# AST-WiFi-Shield.net
KiCad netlist of a schematic drawn in EAGLE
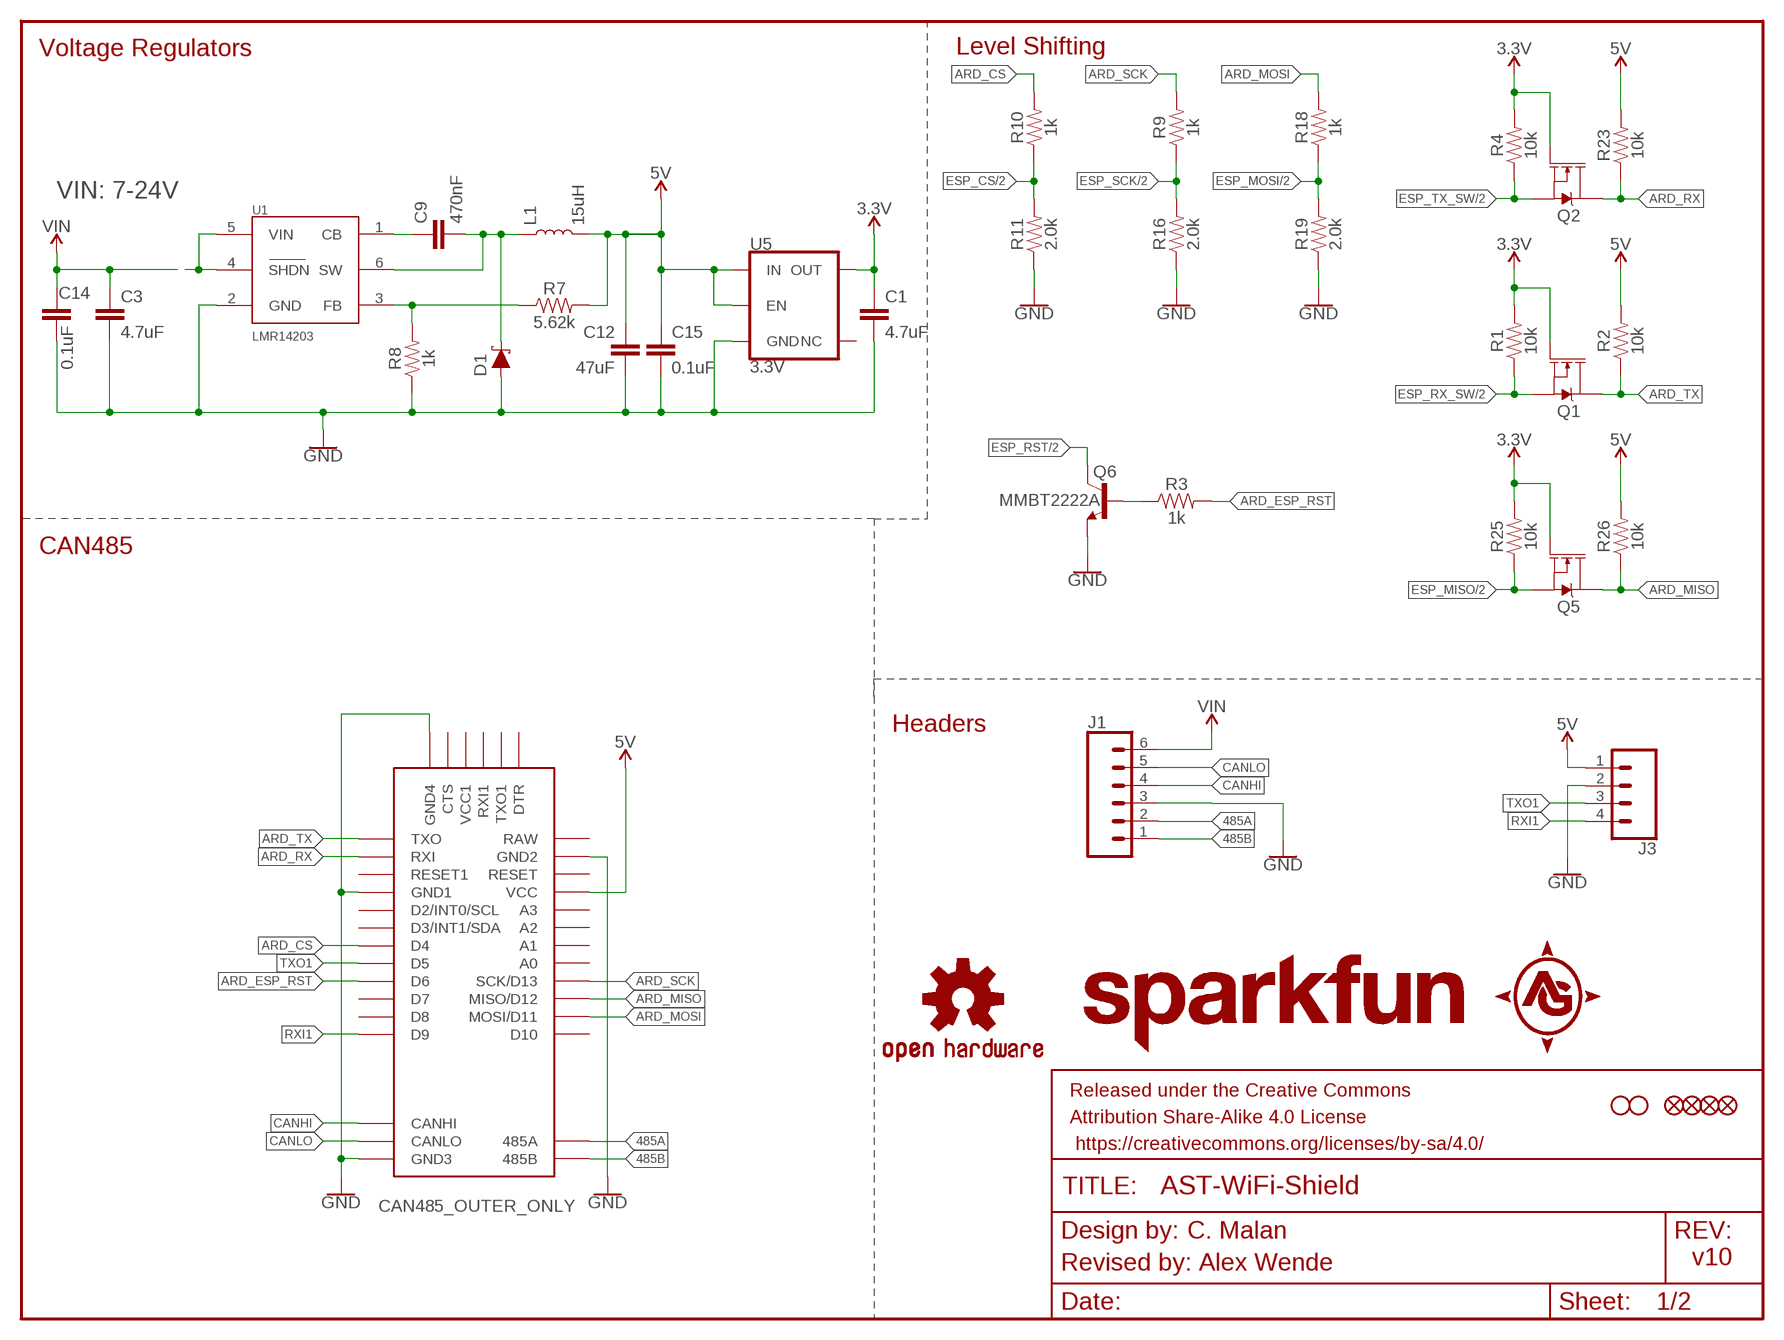
[diagram p0: schematic, sheet 1]
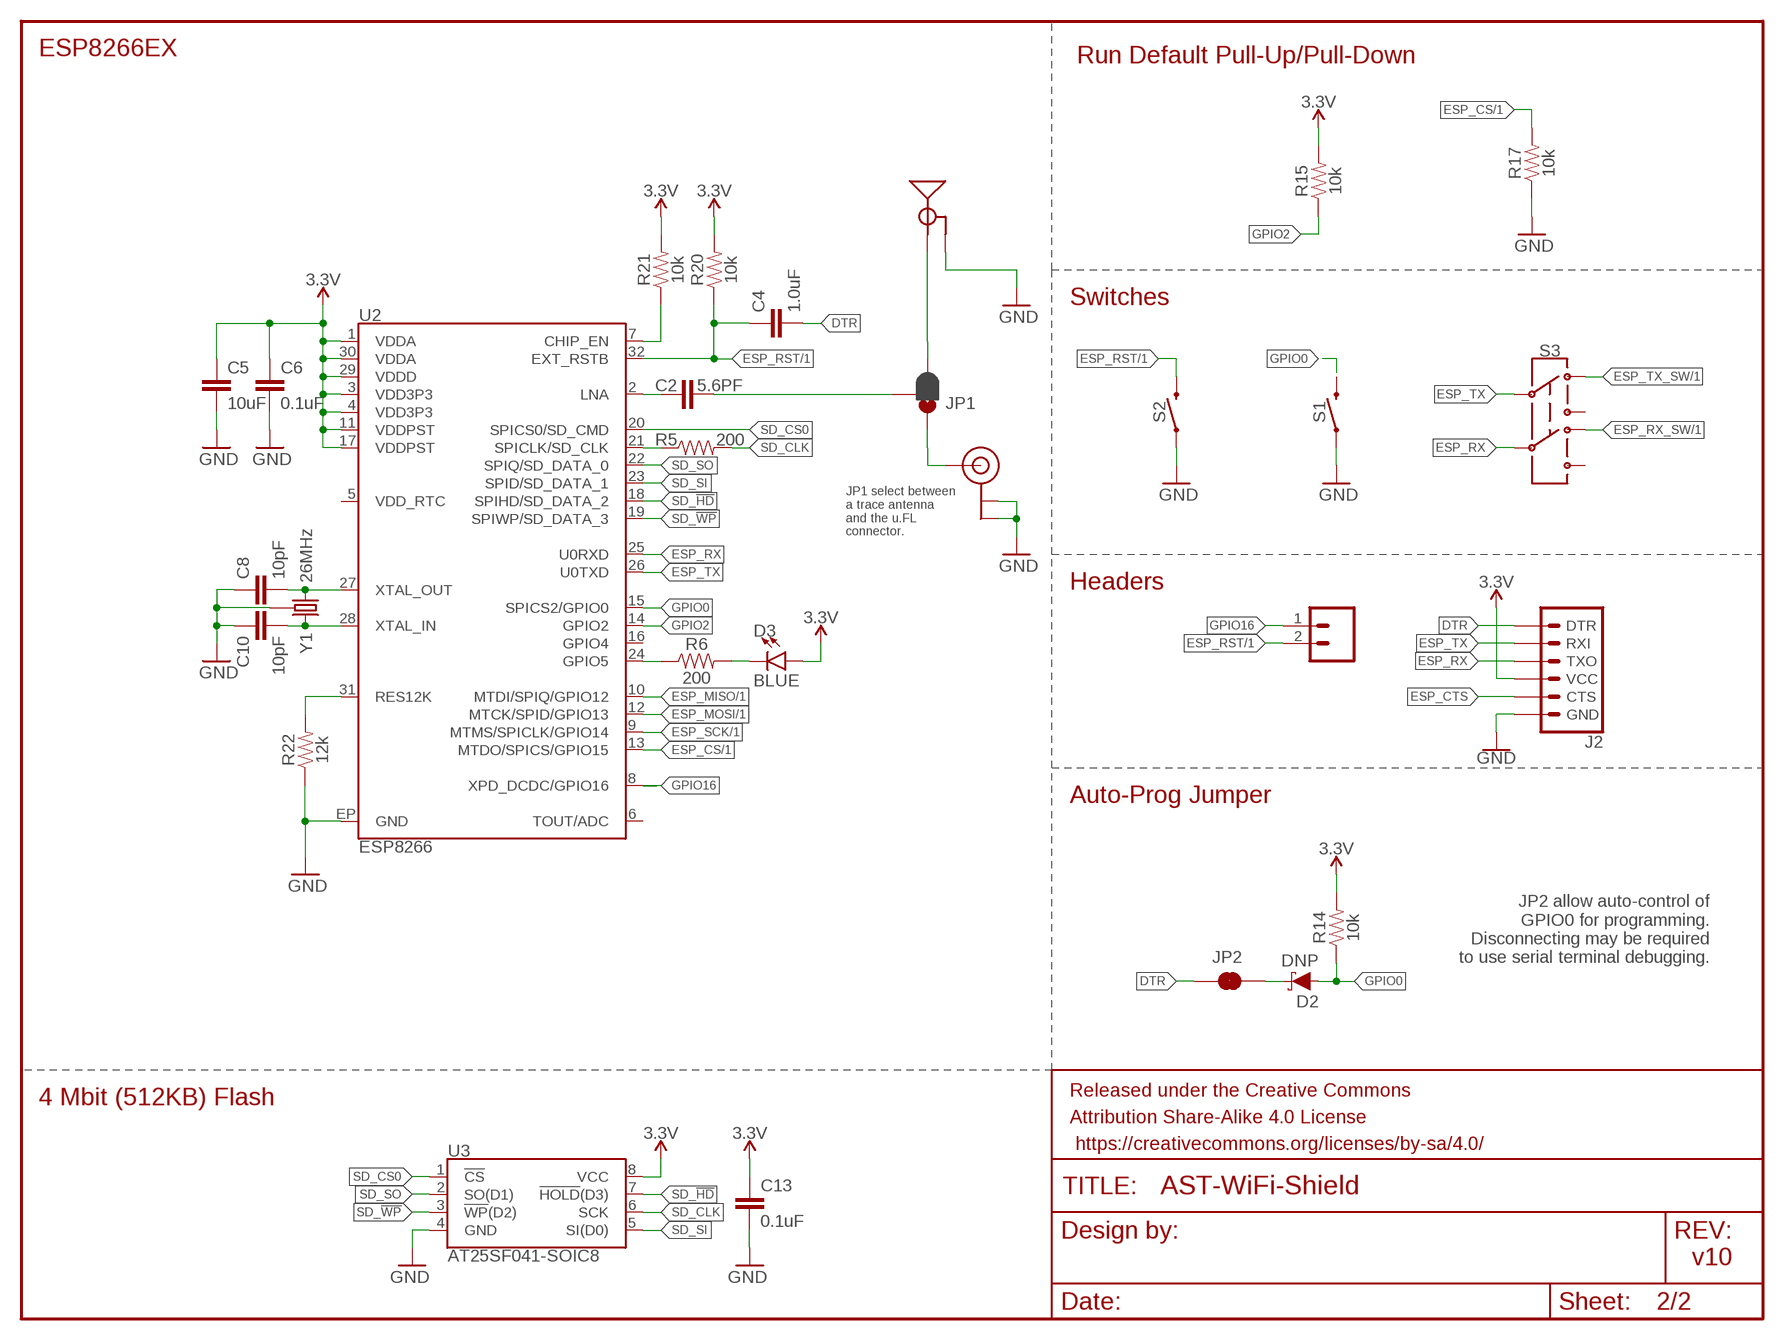
[diagram p1: schematic, sheet 2]

(export (version "E")
  (design (tool "Eeschema 10.0.6"))
  (components
    (comp (ref "C1")
      (value "4.7uF")
      (footprint "eagle-import:0603")
      (libsource (lib "eagle-import") (part "4.7UF-0603-6.3V-(10%)"))
    )
    (comp (ref "C3")
      (value "4.7uF")
      (footprint "eagle-import:0603")
      (libsource (lib "eagle-import") (part "4.7UF-0603-35V-(20%)"))
    )
    (comp (ref "C9")
      (value "470nF")
      (footprint "eagle-import:0603")
      (libsource (lib "eagle-import") (part "470NF-0603-10V-10%-X5R"))
    )
    (comp (ref "C12")
      (value "47uF")
      (footprint "eagle-import:0805")
      (libsource (lib "eagle-import") (part "47UF"))
    )
    (comp (ref "C14")
      (value "0.1uF")
      (footprint "eagle-import:0603")
      (libsource (lib "eagle-import") (part "0.1UF-0603-100V-10%"))
    )
    (comp (ref "C15")
      (value "0.1uF")
      (footprint "eagle-import:0603")
      (libsource (lib "eagle-import") (part "0.1UF-0603-25V-(+80/-20%)"))
    )
    (comp (ref "D1")
      (value "DIODE-SCHOTTKY-MSS1P6-M3/89A")
      (footprint "eagle-import:DIODE-MICRO-SMP")
      (libsource (lib "eagle-import") (part "DIODE-SCHOTTKY-MSS1P6-M3/89A"))
    )
    (comp (ref "FD1")
      (value "FIDUCIALUFIDUCIAL")
      (footprint "eagle-import:FIDUCIAL-MICRO")
      (libsource (lib "eagle-import") (part "FIDUCIALUFIDUCIAL"))
    )
    (comp (ref "FD2")
      (value "FIDUCIALUFIDUCIAL")
      (footprint "eagle-import:FIDUCIAL-MICRO")
      (libsource (lib "eagle-import") (part "FIDUCIALUFIDUCIAL"))
    )
    (comp (ref "FD3")
      (value "FIDUCIALUFIDUCIAL")
      (footprint "eagle-import:FIDUCIAL-MICRO")
      (libsource (lib "eagle-import") (part "FIDUCIALUFIDUCIAL"))
    )
    (comp (ref "FD4")
      (value "FIDUCIALUFIDUCIAL")
      (footprint "eagle-import:FIDUCIAL-MICRO")
      (libsource (lib "eagle-import") (part "FIDUCIALUFIDUCIAL"))
    )
    (comp (ref "FRAME2")
      (value "FRAME-LETTER")
      (footprint "eagle-import:CREATIVE_COMMONS")
      (libsource (lib "eagle-import") (part "FRAME-LETTER"))
    )
    (comp (ref "H1")
      (value "STAND-OFF")
      (footprint "eagle-import:STAND-OFF")
      (libsource (lib "eagle-import") (part "STAND-OFF"))
    )
    (comp (ref "H2")
      (value "STAND-OFF")
      (footprint "eagle-import:STAND-OFF")
      (libsource (lib "eagle-import") (part "STAND-OFF"))
    )
    (comp (ref "J1")
      (value "CONN_063.5MM-6")
      (footprint "eagle-import:SCREWTERMINAL-3.5MM-6")
      (libsource (lib "eagle-import") (part "CONN_063.5MM-6"))
    )
    (comp (ref "J3")
      (value "CONN_04LOCK")
      (footprint "eagle-import:1X04_LOCK")
      (libsource (lib "eagle-import") (part "CONN_04LOCK"))
    )
    (comp (ref "L1")
      (value "15uH")
      (footprint "eagle-import:INDUCTOR_LQH32")
      (libsource (lib "eagle-import") (part "INDUCTOR-LHQ32-15UH"))
    )
    (comp (ref "LOGO1")
      (value "OSHW-LOGOS")
      (footprint "eagle-import:OSHW-LOGO-S")
      (libsource (lib "eagle-import") (part "OSHW-LOGOS"))
    )
    (comp (ref "LOGO2")
      (value "SFE_LOGO_NAME.2_INCH")
      (footprint "eagle-import:SFE_LOGO_NAME_.2")
      (libsource (lib "eagle-import") (part "SFE_LOGO_NAME.2_INCH"))
    )
    (comp (ref "Q1")
      (value "220mA/50V/3.5Ω")
      (footprint "eagle-import:SOT23-3")
      (libsource (lib "eagle-import") (part "MOSFET-NCH-BSS138"))
    )
    (comp (ref "Q2")
      (value "220mA/50V/3.5Ω")
      (footprint "eagle-import:SOT23-3")
      (libsource (lib "eagle-import") (part "MOSFET-NCH-BSS138"))
    )
    (comp (ref "Q5")
      (value "220mA/50V/3.5Ω")
      (footprint "eagle-import:SOT23-3")
      (libsource (lib "eagle-import") (part "MOSFET-NCH-BSS138"))
    )
    (comp (ref "Q6")
      (value "MMBT2222A")
      (footprint "eagle-import:SOT23-3@1")
      (libsource (lib "eagle-import") (part "TRANSISTOR_NPNMMBT2222A"))
    )
    (comp (ref "R1")
      (value "10k")
      (footprint "eagle-import:0603")
      (libsource (lib "eagle-import") (part "10KOHM-0603-1/10W-1%"))
    )
    (comp (ref "R2")
      (value "10k")
      (footprint "eagle-import:0603")
      (libsource (lib "eagle-import") (part "10KOHM-0603-1/10W-1%"))
    )
    (comp (ref "R3")
      (value "1k")
      (footprint "eagle-import:0603")
      (libsource (lib "eagle-import") (part "1KOHM-0603-1/10W-1%"))
    )
    (comp (ref "R4")
      (value "10k")
      (footprint "eagle-import:0603")
      (libsource (lib "eagle-import") (part "10KOHM-0603-1/10W-1%"))
    )
    (comp (ref "R7")
      (value "5.62k")
      (footprint "eagle-import:0603")
      (libsource (lib "eagle-import") (part "5.62KOHM-0603-1/10W-1%"))
    )
    (comp (ref "R8")
      (value "1k")
      (footprint "eagle-import:0603")
      (libsource (lib "eagle-import") (part "1KOHM-0603-1/10W-1%"))
    )
    (comp (ref "R9")
      (value "1k")
      (footprint "eagle-import:0603")
      (libsource (lib "eagle-import") (part "1KOHM-0603-1/10W-1%"))
    )
    (comp (ref "R10")
      (value "1k")
      (footprint "eagle-import:0603")
      (libsource (lib "eagle-import") (part "1KOHM-0603-1/10W-1%"))
    )
    (comp (ref "R11")
      (value "2.0k")
      (footprint "eagle-import:0603")
      (libsource (lib "eagle-import") (part "2.0KOHM-0603-1/10W-5%"))
    )
    (comp (ref "R16")
      (value "2.0k")
      (footprint "eagle-import:0603")
      (libsource (lib "eagle-import") (part "2.0KOHM-0603-1/10W-5%"))
    )
    (comp (ref "R18")
      (value "1k")
      (footprint "eagle-import:0603")
      (libsource (lib "eagle-import") (part "1KOHM-0603-1/10W-1%"))
    )
    (comp (ref "R19")
      (value "2.0k")
      (footprint "eagle-import:0603")
      (libsource (lib "eagle-import") (part "2.0KOHM-0603-1/10W-5%"))
    )
    (comp (ref "R23")
      (value "10k")
      (footprint "eagle-import:0603")
      (libsource (lib "eagle-import") (part "10KOHM-0603-1/10W-1%"))
    )
    (comp (ref "R25")
      (value "10k")
      (footprint "eagle-import:0603")
      (libsource (lib "eagle-import") (part "10KOHM-0603-1/10W-1%"))
    )
    (comp (ref "R26")
      (value "10k")
      (footprint "eagle-import:0603")
      (libsource (lib "eagle-import") (part "10KOHM-0603-1/10W-1%"))
    )
    (comp (ref "U$2")
      (value "CAN485_OUTER_ONLY")
      (footprint "eagle-import:CAN485_OUTER_ONLY")
      (libsource (lib "eagle-import") (part "CAN485_OUTER_ONLY"))
    )
    (comp (ref "U1")
      (value "LMR14203")
      (footprint "eagle-import:SOT23-6")
      (libsource (lib "eagle-import") (part "LMR14203"))
    )
    (comp (ref "U5")
      (value "3.3V")
      (footprint "eagle-import:SOT23-5")
      (libsource (lib "eagle-import") (part "V_REG_AP2112K-3.3V"))
    )
    (comp (ref "C2")
      (value "5.6PF")
      (footprint "eagle-import:0603")
      (libsource (lib "eagle-import") (part "5.6PF-0603-50V-5%"))
    )
    (comp (ref "C4")
      (value "1.0uF")
      (footprint "eagle-import:0603")
      (libsource (lib "eagle-import") (part "1.0UF-0603-16V-10%"))
    )
    (comp (ref "C5")
      (value "10uF")
      (footprint "eagle-import:0603")
      (libsource (lib "eagle-import") (part "10UF-0603-6.3V-20%"))
    )
    (comp (ref "C6")
      (value "0.1uF")
      (footprint "eagle-import:0603")
      (libsource (lib "eagle-import") (part "0.1UF-0603-25V-(+80/-20%)"))
    )
    (comp (ref "C8")
      (value "10pF")
      (footprint "eagle-import:0603")
      (libsource (lib "eagle-import") (part "10PF-0603-50V-5%"))
    )
    (comp (ref "C10")
      (value "10pF")
      (footprint "eagle-import:0603")
      (libsource (lib "eagle-import") (part "10PF-0603-50V-5%"))
    )
    (comp (ref "C13")
      (value "0.1uF")
      (footprint "eagle-import:0603")
      (libsource (lib "eagle-import") (part "0.1UF-0603-25V-(+80/-20%)"))
    )
    (comp (ref "D2")
      (value "DNP")
      (footprint "eagle-import:SOD-323")
      (libsource (lib "eagle-import") (part "DIODE-SCHOTTKY-BAT20J"))
    )
    (comp (ref "D3")
      (value "BLUE")
      (footprint "eagle-import:LED-0603")
      (libsource (lib "eagle-import") (part "LED-BLUE0603"))
    )
    (comp (ref "E1")
      (value "ANTENNATRACE")
      (footprint "eagle-import:TRACE_ANTENNA_2.4GHZ_25.7MM")
      (libsource (lib "eagle-import") (part "ANTENNATRACE"))
    )
    (comp (ref "E2")
      (value "U.FL")
      (footprint "eagle-import:U.FL")
      (libsource (lib "eagle-import") (part "U.FL"))
    )
    (comp (ref "FRAME3")
      (value "FRAME-LETTERNO_PACKAGE")
      (footprint "eagle-import:DUMMY")
      (fields (field (name "DESIGNER") "Nobody"))
      (libsource (lib "eagle-import") (part "FRAME-LETTERNO_PACKAGE"))
    )
    (comp (ref "J2")
      (value "6_PIN_SERIAL_TARGETLOCK")
      (footprint "eagle-import:1X06_LOCK")
      (libsource (lib "eagle-import") (part "6_PIN_SERIAL_TARGETLOCK"))
    )
    (comp (ref "JP1")
      (value "JUMPER-SMT_3_1-NC_PASTE_NO-SILK")
      (footprint "eagle-import:SMT-JUMPER_3_1-NC_PASTE_NO-SILK")
      (libsource (lib "eagle-import") (part "JUMPER-SMT_3_1-NC_PASTE_NO-SILK"))
    )
    (comp (ref "JP2")
      (value "JUMPER-SMT_2_NC_TRACE_NO-SILK")
      (footprint "eagle-import:SMT-JUMPER_2_NC_TRACE_NO-SILK")
      (libsource (lib "eagle-import") (part "JUMPER-SMT_2_NC_TRACE_NO-SILK"))
    )
    (comp (ref "R5")
      (value "200")
      (footprint "eagle-import:0603")
      (libsource (lib "eagle-import") (part "200OHM-0603-1/10W-1%"))
    )
    (comp (ref "R6")
      (value "200")
      (footprint "eagle-import:0603")
      (libsource (lib "eagle-import") (part "200OHM-0603-1/10W-1%"))
    )
    (comp (ref "R14")
      (value "10k")
      (footprint "eagle-import:0603")
      (libsource (lib "eagle-import") (part "10KOHM-0603-1/10W-1%"))
    )
    (comp (ref "R15")
      (value "10k")
      (footprint "eagle-import:0603")
      (libsource (lib "eagle-import") (part "10KOHM-0603-1/10W-1%"))
    )
    (comp (ref "R17")
      (value "10k")
      (footprint "eagle-import:0603")
      (libsource (lib "eagle-import") (part "10KOHM-0603-1/10W-1%"))
    )
    (comp (ref "R20")
      (value "10k")
      (footprint "eagle-import:0603")
      (libsource (lib "eagle-import") (part "10KOHM-0603-1/10W-1%"))
    )
    (comp (ref "R21")
      (value "10k")
      (footprint "eagle-import:0603")
      (libsource (lib "eagle-import") (part "10KOHM-0603-1/10W-1%"))
    )
    (comp (ref "R22")
      (value "12k")
      (footprint "eagle-import:0603")
      (libsource (lib "eagle-import") (part "12KOHM-0603-1/10W-1%"))
    )
    (comp (ref "S1")
      (value "MOMENTARY-SWITCH-SPST-SMD-4.6X2.8MM")
      (footprint "eagle-import:TACTILE_SWITCH_SMD_4.6X2.8MM")
      (libsource (lib "eagle-import") (part "MOMENTARY-SWITCH-SPST-SMD-4.6X2.8MM"))
    )
    (comp (ref "S2")
      (value "MOMENTARY-SWITCH-SPST-SMD-4.6X2.8MM")
      (footprint "eagle-import:TACTILE_SWITCH_SMD_4.6X2.8MM")
      (libsource (lib "eagle-import") (part "MOMENTARY-SWITCH-SPST-SMD-4.6X2.8MM"))
    )
    (comp (ref "S3")
      (value "SWITCH-DPDT-SMD-JS202011JCQN")
      (footprint "eagle-import:SWITCH_DPDT_SMD_JS202011JCQN")
      (libsource (lib "eagle-import") (part "SWITCH-DPDT-SMD-JS202011JCQN"))
    )
    (comp (ref "SJ2")
      (value "SLEEP-PTH")
      (footprint "eagle-import:1X02_NO_SILK")
      (libsource (lib "eagle-import") (part "CONN_021X02_NO_SILK"))
    )
    (comp (ref "U2")
      (value "ESP8266")
      (footprint "eagle-import:QFN32")
      (fields (field (name "PROD_ID") "IC-12452"))
      (libsource (lib "eagle-import") (part "ESP8266"))
    )
    (comp (ref "U3")
      (value "AT25SF041-SOIC8")
      (footprint "eagle-import:SO08")
      (fields (field (name "PROD_ID") "IC-12455"))
      (libsource (lib "eagle-import") (part "AT25SF041-SOIC8"))
    )
    (comp (ref "Y1")
      (value "26MHz")
      (footprint "eagle-import:CRYSTAL-SMD-3.2X2.5")
      (fields (field (name "PROD_ID") "XTAL-12454"))
      (libsource (lib "eagle-import") (part "CRYSTAL-GROUNDED3.2X2.5"))
    )
  )
  (nets
    (net (code "1") (name "3.3V") (class "Default")
      (node (ref "C1") (pin "1") (pinfunction "1_1") (pintype "passive"))
      (node (ref "C13") (pin "1") (pinfunction "1_1") (pintype "passive"))
      (node (ref "C5") (pin "1") (pinfunction "1_1") (pintype "passive"))
      (node (ref "C6") (pin "1") (pinfunction "1_1") (pintype "passive"))
      (node (ref "D3") (pin "A") (pinfunction "A_A") (pintype "passive"))
      (node (ref "J2") (pin "4") (pinfunction "VCC_4") (pintype "passive"))
      (node (ref "Q1") (pin "1") (pinfunction "G_1") (pintype "bidirectional"))
      (node (ref "Q2") (pin "1") (pinfunction "G_1") (pintype "bidirectional"))
      (node (ref "Q5") (pin "1") (pinfunction "G_1") (pintype "bidirectional"))
      (node (ref "R1") (pin "2") (pinfunction "2_2") (pintype "passive"))
      (node (ref "R14") (pin "2") (pinfunction "2_2") (pintype "passive"))
      (node (ref "R15") (pin "2") (pinfunction "2_2") (pintype "passive"))
      (node (ref "R20") (pin "2") (pinfunction "2_2") (pintype "passive"))
      (node (ref "R21") (pin "2") (pinfunction "2_2") (pintype "passive"))
      (node (ref "R25") (pin "2") (pinfunction "2_2") (pintype "passive"))
      (node (ref "R4") (pin "2") (pinfunction "2_2") (pintype "passive"))
      (node (ref "U2") (pin "1") (pinfunction "VDDA_1") (pintype "bidirectional"))
      (node (ref "U2") (pin "11") (pinfunction "VDDPST_11") (pintype "bidirectional"))
      (node (ref "U2") (pin "17") (pinfunction "VDDPST_17") (pintype "bidirectional"))
      (node (ref "U2") (pin "29") (pinfunction "VDDD_29") (pintype "bidirectional"))
      (node (ref "U2") (pin "3") (pinfunction "VDD3P3_3") (pintype "bidirectional"))
      (node (ref "U2") (pin "30") (pinfunction "VDDA_30") (pintype "bidirectional"))
      (node (ref "U2") (pin "4") (pinfunction "VDD3P3_4") (pintype "bidirectional"))
      (node (ref "U3") (pin "8") (pinfunction "VCC_8") (pintype "bidirectional"))
      (node (ref "U5") (pin "5") (pinfunction "OUT_5") (pintype "passive"))
    )
    (net (code "2") (name "5V") (class "Default")
      (node (ref "C12") (pin "1") (pinfunction "1_1") (pintype "passive"))
      (node (ref "C15") (pin "1") (pinfunction "1_1") (pintype "passive"))
      (node (ref "J3") (pin "1") (pinfunction "1_1") (pintype "passive"))
      (node (ref "L1") (pin "P$2") (pinfunction "2_P$2") (pintype "passive"))
      (node (ref "R2") (pin "2") (pinfunction "2_2") (pintype "passive"))
      (node (ref "R23") (pin "2") (pinfunction "2_2") (pintype "passive"))
      (node (ref "R26") (pin "2") (pinfunction "2_2") (pintype "passive"))
      (node (ref "R7") (pin "2") (pinfunction "2_2") (pintype "passive"))
      (node (ref "U$2") (pin "VCC") (pinfunction "VCC_VCC") (pintype "bidirectional"))
      (node (ref "U5") (pin "1") (pinfunction "IN_1") (pintype "input"))
      (node (ref "U5") (pin "3") (pinfunction "EN_3") (pintype "input"))
    )
    (net (code "3") (name "485A") (class "Default")
      (node (ref "J1") (pin "2") (pinfunction "2_2") (pintype "passive"))
      (node (ref "U$2") (pin "485A") (pinfunction "485A_485A") (pintype "bidirectional"))
    )
    (net (code "4") (name "485B") (class "Default")
      (node (ref "J1") (pin "1") (pinfunction "1_1") (pintype "passive"))
      (node (ref "U$2") (pin "485B") (pinfunction "485B_485B") (pintype "bidirectional"))
    )
    (net (code "5") (name "ARD_CS") (class "Default")
      (node (ref "R10") (pin "2") (pinfunction "2_2") (pintype "passive"))
      (node (ref "U$2") (pin "4") (pinfunction "D4_4") (pintype "bidirectional"))
    )
    (net (code "6") (name "ARD_ESP_RST") (class "Default")
      (node (ref "R3") (pin "2") (pinfunction "2_2") (pintype "passive"))
      (node (ref "U$2") (pin "6") (pinfunction "D6_6") (pintype "bidirectional"))
    )
    (net (code "7") (name "ARD_MISO") (class "Default")
      (node (ref "Q5") (pin "3") (pinfunction "D_3") (pintype "bidirectional"))
      (node (ref "R26") (pin "1") (pinfunction "1_1") (pintype "passive"))
      (node (ref "U$2") (pin "12") (pinfunction "MISO/D12_12") (pintype "bidirectional"))
    )
    (net (code "8") (name "ARD_MOSI") (class "Default")
      (node (ref "R18") (pin "2") (pinfunction "2_2") (pintype "passive"))
      (node (ref "U$2") (pin "11") (pinfunction "MOSI/D11_11") (pintype "bidirectional"))
    )
    (net (code "9") (name "ARD_RX") (class "Default")
      (node (ref "Q2") (pin "3") (pinfunction "D_3") (pintype "bidirectional"))
      (node (ref "R23") (pin "1") (pinfunction "1_1") (pintype "passive"))
      (node (ref "U$2") (pin "RXI") (pinfunction "RXI_RXI") (pintype "bidirectional"))
    )
    (net (code "10") (name "ARD_SCK") (class "Default")
      (node (ref "R9") (pin "2") (pinfunction "2_2") (pintype "passive"))
      (node (ref "U$2") (pin "13") (pinfunction "SCK/D13_13") (pintype "bidirectional"))
    )
    (net (code "11") (name "ARD_TX") (class "Default")
      (node (ref "Q1") (pin "3") (pinfunction "D_3") (pintype "bidirectional"))
      (node (ref "R2") (pin "1") (pinfunction "1_1") (pintype "passive"))
      (node (ref "U$2") (pin "TXO") (pinfunction "TXO_TXO") (pintype "bidirectional"))
    )
    (net (code "12") (name "CANHI") (class "Default")
      (node (ref "J1") (pin "4") (pinfunction "4_4") (pintype "passive"))
      (node (ref "U$2") (pin "CANHI") (pinfunction "CANHI_CANHI") (pintype "bidirectional"))
    )
    (net (code "13") (name "CANLO") (class "Default")
      (node (ref "J1") (pin "5") (pinfunction "5_5") (pintype "passive"))
      (node (ref "U$2") (pin "CANLO") (pinfunction "CANLO_CANLO") (pintype "bidirectional"))
    )
    (net (code "14") (name "DTR") (class "Default")
      (node (ref "C4") (pin "2") (pinfunction "2_2") (pintype "passive"))
      (node (ref "J2") (pin "1") (pinfunction "DTR_1") (pintype "passive"))
      (node (ref "JP2") (pin "1") (pinfunction "1_1") (pintype "passive"))
    )
    (net (code "15") (name "ESP_CS") (class "Default")
      (node (ref "R10") (pin "1") (pinfunction "1_1") (pintype "passive"))
      (node (ref "R11") (pin "2") (pinfunction "2_2") (pintype "passive"))
      (node (ref "R17") (pin "2") (pinfunction "2_2") (pintype "passive"))
      (node (ref "U2") (pin "13") (pinfunction "MTDO/SPICS/GPIO15_13") (pintype "bidirectional"))
    )
    (net (code "16") (name "ESP_CTS") (class "Default")
      (node (ref "J2") (pin "5") (pinfunction "CTS_5") (pintype "passive"))
    )
    (net (code "17") (name "ESP_MISO") (class "Default")
      (node (ref "Q5") (pin "2") (pinfunction "S_2") (pintype "bidirectional"))
      (node (ref "R25") (pin "1") (pinfunction "1_1") (pintype "passive"))
      (node (ref "U2") (pin "10") (pinfunction "MTDI/SPIQ/GPIO12_10") (pintype "bidirectional"))
    )
    (net (code "18") (name "ESP_MOSI") (class "Default")
      (node (ref "R18") (pin "1") (pinfunction "1_1") (pintype "passive"))
      (node (ref "R19") (pin "2") (pinfunction "2_2") (pintype "passive"))
      (node (ref "U2") (pin "12") (pinfunction "MTCK/SPID/GPIO13_12") (pintype "bidirectional"))
    )
    (net (code "19") (name "ESP_RST") (class "Default")
      (node (ref "C4") (pin "1") (pinfunction "1_1") (pintype "passive"))
      (node (ref "Q6") (pin "3") (pinfunction "C_3") (pintype "passive"))
      (node (ref "R20") (pin "1") (pinfunction "1_1") (pintype "passive"))
      (node (ref "S2") (pin "3") (pinfunction "2_3") (pintype "passive"))
      (node (ref "S2") (pin "4") (pinfunction "2_4") (pintype "passive"))
      (node (ref "SJ2") (pin "2") (pinfunction "2_2") (pintype "passive"))
      (node (ref "U2") (pin "32") (pinfunction "EXT_RSTB_32") (pintype "bidirectional"))
    )
    (net (code "20") (name "ESP_RX") (class "Default")
      (node (ref "J2") (pin "3") (pinfunction "TXO_3") (pintype "passive"))
      (node (ref "S3") (pin "5") (pinfunction "5_5") (pintype "bidirectional"))
      (node (ref "U2") (pin "25") (pinfunction "U0RXD_25") (pintype "bidirectional"))
    )
    (net (code "21") (name "ESP_RX_SW") (class "Default")
      (node (ref "Q1") (pin "2") (pinfunction "S_2") (pintype "bidirectional"))
      (node (ref "R1") (pin "1") (pinfunction "1_1") (pintype "passive"))
      (node (ref "S3") (pin "6") (pinfunction "4_6") (pintype "bidirectional"))
    )
    (net (code "22") (name "ESP_SCK") (class "Default")
      (node (ref "R16") (pin "2") (pinfunction "2_2") (pintype "passive"))
      (node (ref "R9") (pin "1") (pinfunction "1_1") (pintype "passive"))
      (node (ref "U2") (pin "9") (pinfunction "MTMS/SPICLK/GPIO14_9") (pintype "bidirectional"))
    )
    (net (code "23") (name "ESP_TX") (class "Default")
      (node (ref "J2") (pin "2") (pinfunction "RXI_2") (pintype "passive"))
      (node (ref "S3") (pin "2") (pinfunction "2_2") (pintype "bidirectional"))
      (node (ref "U2") (pin "26") (pinfunction "U0TXD_26") (pintype "bidirectional"))
    )
    (net (code "24") (name "ESP_TX_SW") (class "Default")
      (node (ref "Q2") (pin "2") (pinfunction "S_2") (pintype "bidirectional"))
      (node (ref "R4") (pin "1") (pinfunction "1_1") (pintype "passive"))
      (node (ref "S3") (pin "1") (pinfunction "1_1") (pintype "bidirectional"))
    )
    (net (code "25") (name "GND") (class "Default")
      (node (ref "C1") (pin "2") (pinfunction "2_2") (pintype "passive"))
      (node (ref "C10") (pin "1") (pinfunction "1_1") (pintype "passive"))
      (node (ref "C12") (pin "2") (pinfunction "2_2") (pintype "passive"))
      (node (ref "C13") (pin "2") (pinfunction "2_2") (pintype "passive"))
      (node (ref "C14") (pin "2") (pinfunction "2_2") (pintype "passive"))
      (node (ref "C15") (pin "2") (pinfunction "2_2") (pintype "passive"))
      (node (ref "C3") (pin "2") (pinfunction "2_2") (pintype "passive"))
      (node (ref "C5") (pin "2") (pinfunction "2_2") (pintype "passive"))
      (node (ref "C6") (pin "2") (pinfunction "2_2") (pintype "passive"))
      (node (ref "C8") (pin "1") (pinfunction "1_1") (pintype "passive"))
      (node (ref "D1") (pin "A") (pinfunction "A_A") (pintype "passive"))
      (node (ref "E1") (pin "GND") (pinfunction "GND_GND") (pintype "bidirectional"))
      (node (ref "E1") (pin "GND2") (pinfunction "GND_GND2") (pintype "bidirectional"))
      (node (ref "E2") (pin "1") (pinfunction "GND_1") (pintype "bidirectional"))
      (node (ref "E2") (pin "2") (pinfunction "GND_2") (pintype "bidirectional"))
      (node (ref "J1") (pin "3") (pinfunction "3_3") (pintype "passive"))
      (node (ref "J2") (pin "6") (pinfunction "GND_6") (pintype "passive"))
      (node (ref "J3") (pin "2") (pinfunction "2_2") (pintype "passive"))
      (node (ref "Q6") (pin "2") (pinfunction "E_2") (pintype "passive"))
      (node (ref "R11") (pin "1") (pinfunction "1_1") (pintype "passive"))
      (node (ref "R16") (pin "1") (pinfunction "1_1") (pintype "passive"))
      (node (ref "R17") (pin "1") (pinfunction "1_1") (pintype "passive"))
      (node (ref "R19") (pin "1") (pinfunction "1_1") (pintype "passive"))
      (node (ref "R22") (pin "1") (pinfunction "1_1") (pintype "passive"))
      (node (ref "R8") (pin "1") (pinfunction "1_1") (pintype "passive"))
      (node (ref "S1") (pin "1") (pinfunction "1_1") (pintype "passive"))
      (node (ref "S1") (pin "2") (pinfunction "1_2") (pintype "passive"))
      (node (ref "S2") (pin "1") (pinfunction "1_1") (pintype "passive"))
      (node (ref "S2") (pin "2") (pinfunction "1_2") (pintype "passive"))
      (node (ref "U$2") (pin "GND1") (pinfunction "GND1_GND1") (pintype "bidirectional"))
      (node (ref "U$2") (pin "GND2") (pinfunction "GND2_GND2") (pintype "bidirectional"))
      (node (ref "U$2") (pin "GND3") (pinfunction "GND3_GND3") (pintype "bidirectional"))
      (node (ref "U$2") (pin "GND4") (pinfunction "GND4_GND4") (pintype "bidirectional"))
      (node (ref "U1") (pin "2") (pinfunction "GND_2") (pintype "power_in"))
      (node (ref "U2") (pin "EP") (pinfunction "GND_EP") (pintype "bidirectional"))
      (node (ref "U3") (pin "4") (pinfunction "GND_4") (pintype "bidirectional"))
      (node (ref "U5") (pin "2") (pinfunction "GND_2") (pintype "input"))
      (node (ref "Y1") (pin "2") (pinfunction "GND_2") (pintype "passive"))
      (node (ref "Y1") (pin "4") (pinfunction "GND_4") (pintype "passive"))
    )
    (net (code "26") (name "GPIO0") (class "Default")
      (node (ref "D2") (pin "A") (pinfunction "A_A") (pintype "passive"))
      (node (ref "R14") (pin "1") (pinfunction "1_1") (pintype "passive"))
      (node (ref "S1") (pin "3") (pinfunction "2_3") (pintype "passive"))
      (node (ref "S1") (pin "4") (pinfunction "2_4") (pintype "passive"))
      (node (ref "U2") (pin "15") (pinfunction "SPICS2/GPIO0_15") (pintype "bidirectional"))
    )
    (net (code "27") (name "GPIO2") (class "Default")
      (node (ref "R15") (pin "1") (pinfunction "1_1") (pintype "passive"))
      (node (ref "U2") (pin "14") (pinfunction "GPIO2_14") (pintype "bidirectional"))
    )
    (net (code "28") (name "GPIO16") (class "Default")
      (node (ref "SJ2") (pin "1") (pinfunction "1_1") (pintype "passive"))
      (node (ref "U2") (pin "8") (pinfunction "XPD_DCDC/GPIO16_8") (pintype "bidirectional"))
    )
    (net (code "29") (name "Net-(C2-Pad2)") (class "Default")
      (node (ref "C2") (pin "2") (pinfunction "2_2") (pintype "passive"))
      (node (ref "JP1") (pin "2") (pinfunction "2_2") (pintype "passive"))
    )
    (net (code "30") (name "Net-(D2-PadC)") (class "Default")
      (node (ref "D2") (pin "C") (pinfunction "C_C") (pintype "passive"))
      (node (ref "JP2") (pin "2") (pinfunction "2_2") (pintype "passive"))
    )
    (net (code "31") (name "Net-(D3-PadC)") (class "Default")
      (node (ref "D3") (pin "C") (pinfunction "C_C") (pintype "passive"))
      (node (ref "R6") (pin "2") (pinfunction "2_2") (pintype "passive"))
    )
    (net (code "32") (name "Net-(E1-SIGNAL)") (class "Default")
      (node (ref "E1") (pin "ANT") (pinfunction "SIGNAL_ANT") (pintype "bidirectional"))
      (node (ref "JP1") (pin "3") (pinfunction "3_3") (pintype "passive"))
    )
    (net (code "33") (name "Net-(E2-SIGNAL)") (class "Default")
      (node (ref "E2") (pin "FEED") (pinfunction "SIGNAL_FEED") (pintype "bidirectional"))
      (node (ref "JP1") (pin "1") (pinfunction "1_1") (pintype "passive"))
    )
    (net (code "34") (name "Net-(L1-1)") (class "Default")
      (node (ref "C9") (pin "2") (pinfunction "2_2") (pintype "passive"))
      (node (ref "D1") (pin "C") (pinfunction "C_C") (pintype "passive"))
      (node (ref "L1") (pin "P$1") (pinfunction "1_P$1") (pintype "passive"))
      (node (ref "U1") (pin "6") (pinfunction "SW_6") (pintype "power_in"))
    )
    (net (code "35") (name "Net-(Q6-B)") (class "Default")
      (node (ref "Q6") (pin "1") (pinfunction "B_1") (pintype "passive"))
      (node (ref "R3") (pin "1") (pinfunction "1_1") (pintype "passive"))
    )
    (net (code "36") (name "Net-(U1-CB)") (class "Default")
      (node (ref "C9") (pin "1") (pinfunction "1_1") (pintype "passive"))
      (node (ref "U1") (pin "1") (pinfunction "CB_1") (pintype "input"))
    )
    (net (code "37") (name "Net-(U1-FB)") (class "Default")
      (node (ref "R7") (pin "1") (pinfunction "1_1") (pintype "passive"))
      (node (ref "R8") (pin "2") (pinfunction "2_2") (pintype "passive"))
      (node (ref "U1") (pin "3") (pinfunction "FB_3") (pintype "input"))
    )
    (net (code "38") (name "Net-(U2-CHIP_EN)") (class "Default")
      (node (ref "R21") (pin "1") (pinfunction "1_1") (pintype "passive"))
      (node (ref "U2") (pin "7") (pinfunction "CHIP_EN_7") (pintype "bidirectional"))
    )
    (net (code "39") (name "Net-(U2-GPIO5)") (class "Default")
      (node (ref "R6") (pin "1") (pinfunction "1_1") (pintype "passive"))
      (node (ref "U2") (pin "24") (pinfunction "GPIO5_24") (pintype "bidirectional"))
    )
    (net (code "40") (name "Net-(U2-LNA)") (class "Default")
      (node (ref "C2") (pin "1") (pinfunction "1_1") (pintype "passive"))
      (node (ref "U2") (pin "2") (pinfunction "LNA_2") (pintype "bidirectional"))
    )
    (net (code "41") (name "Net-(U2-RES12K)") (class "Default")
      (node (ref "R22") (pin "2") (pinfunction "2_2") (pintype "passive"))
      (node (ref "U2") (pin "31") (pinfunction "RES12K_31") (pintype "bidirectional"))
    )
    (net (code "42") (name "Net-(U2-SPICLK{slash}SD_CLK)") (class "Default")
      (node (ref "R5") (pin "1") (pinfunction "1_1") (pintype "passive"))
      (node (ref "U2") (pin "21") (pinfunction "SPICLK/SD_CLK_21") (pintype "bidirectional"))
    )
    (net (code "43") (name "Net-(U2-XTAL_IN)") (class "Default")
      (node (ref "C10") (pin "2") (pinfunction "2_2") (pintype "passive"))
      (node (ref "U2") (pin "28") (pinfunction "XTAL_IN_28") (pintype "bidirectional"))
      (node (ref "Y1") (pin "3") (pinfunction "2_3") (pintype "passive"))
    )
    (net (code "44") (name "Net-(U2-XTAL_OUT)") (class "Default")
      (node (ref "C8") (pin "2") (pinfunction "2_2") (pintype "passive"))
      (node (ref "U2") (pin "27") (pinfunction "XTAL_OUT_27") (pintype "bidirectional"))
      (node (ref "Y1") (pin "1") (pinfunction "1_1") (pintype "passive"))
    )
    (net (code "45") (name "RXI1") (class "Default")
      (node (ref "J3") (pin "4") (pinfunction "4_4") (pintype "passive"))
      (node (ref "U$2") (pin "9") (pinfunction "D9_9") (pintype "bidirectional"))
    )
    (net (code "46") (name "SD_CLK") (class "Default")
      (node (ref "R5") (pin "2") (pinfunction "2_2") (pintype "passive"))
      (node (ref "U3") (pin "6") (pinfunction "SCK_6") (pintype "bidirectional"))
    )
    (net (code "47") (name "SD_CS0") (class "Default")
      (node (ref "U2") (pin "20") (pinfunction "SPICS0/SD_CMD_20") (pintype "bidirectional"))
      (node (ref "U3") (pin "1") (pinfunction "~{CS}_1") (pintype "bidirectional"))
    )
    (net (code "48") (name "SD_SI") (class "Default")
      (node (ref "U2") (pin "23") (pinfunction "SPID/SD_DATA_1_23") (pintype "bidirectional"))
      (node (ref "U3") (pin "5") (pinfunction "SI(D0)_5") (pintype "bidirectional"))
    )
    (net (code "49") (name "SD_SO") (class "Default")
      (node (ref "U2") (pin "22") (pinfunction "SPIQ/SD_DATA_0_22") (pintype "bidirectional"))
      (node (ref "U3") (pin "2") (pinfunction "SO(D1)_2") (pintype "bidirectional"))
    )
    (net (code "50") (name "SD_~{HD}") (class "Default")
      (node (ref "U2") (pin "18") (pinfunction "SPIHD/SD_DATA_2_18") (pintype "bidirectional"))
      (node (ref "U3") (pin "7") (pinfunction "~{HOLD}(D3)_7") (pintype "bidirectional"))
    )
    (net (code "51") (name "SD_~{WP}") (class "Default")
      (node (ref "U2") (pin "19") (pinfunction "SPIWP/SD_DATA_3_19") (pintype "bidirectional"))
      (node (ref "U3") (pin "3") (pinfunction "~{WP}(D2)_3") (pintype "bidirectional"))
    )
    (net (code "52") (name "TXO1") (class "Default")
      (node (ref "J3") (pin "3") (pinfunction "3_3") (pintype "passive"))
      (node (ref "U$2") (pin "5") (pinfunction "D5_5") (pintype "bidirectional"))
    )
    (net (code "53") (name "VIN") (class "Default")
      (node (ref "C14") (pin "1") (pinfunction "1_1") (pintype "passive"))
      (node (ref "C3") (pin "1") (pinfunction "1_1") (pintype "passive"))
      (node (ref "J1") (pin "6") (pinfunction "6_6") (pintype "passive"))
      (node (ref "U1") (pin "4") (pinfunction "SHDN_4") (pintype "input"))
      (node (ref "U1") (pin "5") (pinfunction "VIN_5") (pintype "power_in"))
    )
    (net (code "54") (name "unconnected-(S3-6-Pad4)") (class "Default")
      (node (ref "S3") (pin "4") (pinfunction "6_4") (pintype "bidirectional"))
    )
    (net (code "55") (name "unconnected-(S3-Pad3)") (class "Default")
      (node (ref "S3") (pin "3") (pinfunction "3_3") (pintype "bidirectional"))
    )
    (net (code "56") (name "unconnected-(U$2-D2{slash}INT0{slash}SCL-Pad2)") (class "Default")
      (node (ref "U$2") (pin "2") (pinfunction "D2/INT0/SCL_2") (pintype "bidirectional"))
    )
    (net (code "57") (name "unconnected-(U$2-D3{slash}INT1{slash}SDA-Pad3)") (class "Default")
      (node (ref "U$2") (pin "3") (pinfunction "D3/INT1/SDA_3") (pintype "bidirectional"))
    )
    (net (code "58") (name "unconnected-(U$2-D7-Pad7)") (class "Default")
      (node (ref "U$2") (pin "7") (pinfunction "D7_7") (pintype "bidirectional"))
    )
    (net (code "59") (name "unconnected-(U$2-D8-Pad8)") (class "Default")
      (node (ref "U$2") (pin "8") (pinfunction "D8_8") (pintype "bidirectional"))
    )
    (net (code "60") (name "unconnected-(U$2-D10-Pad10)") (class "Default")
      (node (ref "U$2") (pin "10") (pinfunction "D10_10") (pintype "bidirectional"))
    )
    (net (code "61") (name "unconnected-(U$2-PadA0)") (class "Default")
      (node (ref "U$2") (pin "A0") (pinfunction "A0_A0") (pintype "bidirectional"))
    )
    (net (code "62") (name "unconnected-(U$2-PadA1)") (class "Default")
      (node (ref "U$2") (pin "A1") (pinfunction "A1_A1") (pintype "bidirectional"))
    )
    (net (code "63") (name "unconnected-(U$2-PadA2)") (class "Default")
      (node (ref "U$2") (pin "A2") (pinfunction "A2_A2") (pintype "bidirectional"))
    )
    (net (code "64") (name "unconnected-(U$2-PadA3)") (class "Default")
      (node (ref "U$2") (pin "A3") (pinfunction "A3_A3") (pintype "bidirectional"))
    )
    (net (code "65") (name "unconnected-(U$2-PadCTS)") (class "Default")
      (node (ref "U$2") (pin "CTS") (pinfunction "CTS_CTS") (pintype "bidirectional"))
    )
    (net (code "66") (name "unconnected-(U$2-PadDTR)") (class "Default")
      (node (ref "U$2") (pin "DTR") (pinfunction "DTR_DTR") (pintype "bidirectional"))
    )
    (net (code "67") (name "unconnected-(U$2-PadRAW)") (class "Default")
      (node (ref "U$2") (pin "RAW") (pinfunction "RAW_RAW") (pintype "bidirectional"))
    )
    (net (code "68") (name "unconnected-(U$2-PadRXI1)") (class "Default")
      (node (ref "U$2") (pin "RXI1") (pinfunction "RXI1_RXI1") (pintype "bidirectional"))
    )
    (net (code "69") (name "unconnected-(U$2-PadTXO1)") (class "Default")
      (node (ref "U$2") (pin "TXO1") (pinfunction "TXO1_TXO1") (pintype "bidirectional"))
    )
    (net (code "70") (name "unconnected-(U$2-PadVCC1)") (class "Default")
      (node (ref "U$2") (pin "VCC1") (pinfunction "VCC1_VCC1") (pintype "bidirectional"))
    )
    (net (code "71") (name "unconnected-(U$2-RESET-PadRST)") (class "Default")
      (node (ref "U$2") (pin "RST") (pinfunction "RESET_RST") (pintype "bidirectional"))
    )
    (net (code "72") (name "unconnected-(U$2-RESET1-PadRST1)") (class "Default")
      (node (ref "U$2") (pin "RST1") (pinfunction "RESET1_RST1") (pintype "bidirectional"))
    )
    (net (code "73") (name "unconnected-(U2-GPIO4-Pad16)") (class "Default")
      (node (ref "U2") (pin "16") (pinfunction "GPIO4_16") (pintype "bidirectional"))
    )
    (net (code "74") (name "unconnected-(U2-TOUT{slash}ADC-Pad6)") (class "Default")
      (node (ref "U2") (pin "6") (pinfunction "TOUT/ADC_6") (pintype "bidirectional"))
    )
    (net (code "75") (name "unconnected-(U2-VDD_RTC-Pad5)") (class "Default")
      (node (ref "U2") (pin "5") (pinfunction "VDD_RTC_5") (pintype "bidirectional"))
    )
    (net (code "76") (name "unconnected-(U5-NC-Pad4)") (class "Default")
      (node (ref "U5") (pin "4") (pinfunction "NC_4") (pintype "no_connect"))
    )
  )
)
